# 07_USB_To_UART.net
KiCad netlist of a schematic drawn in Altium Designer
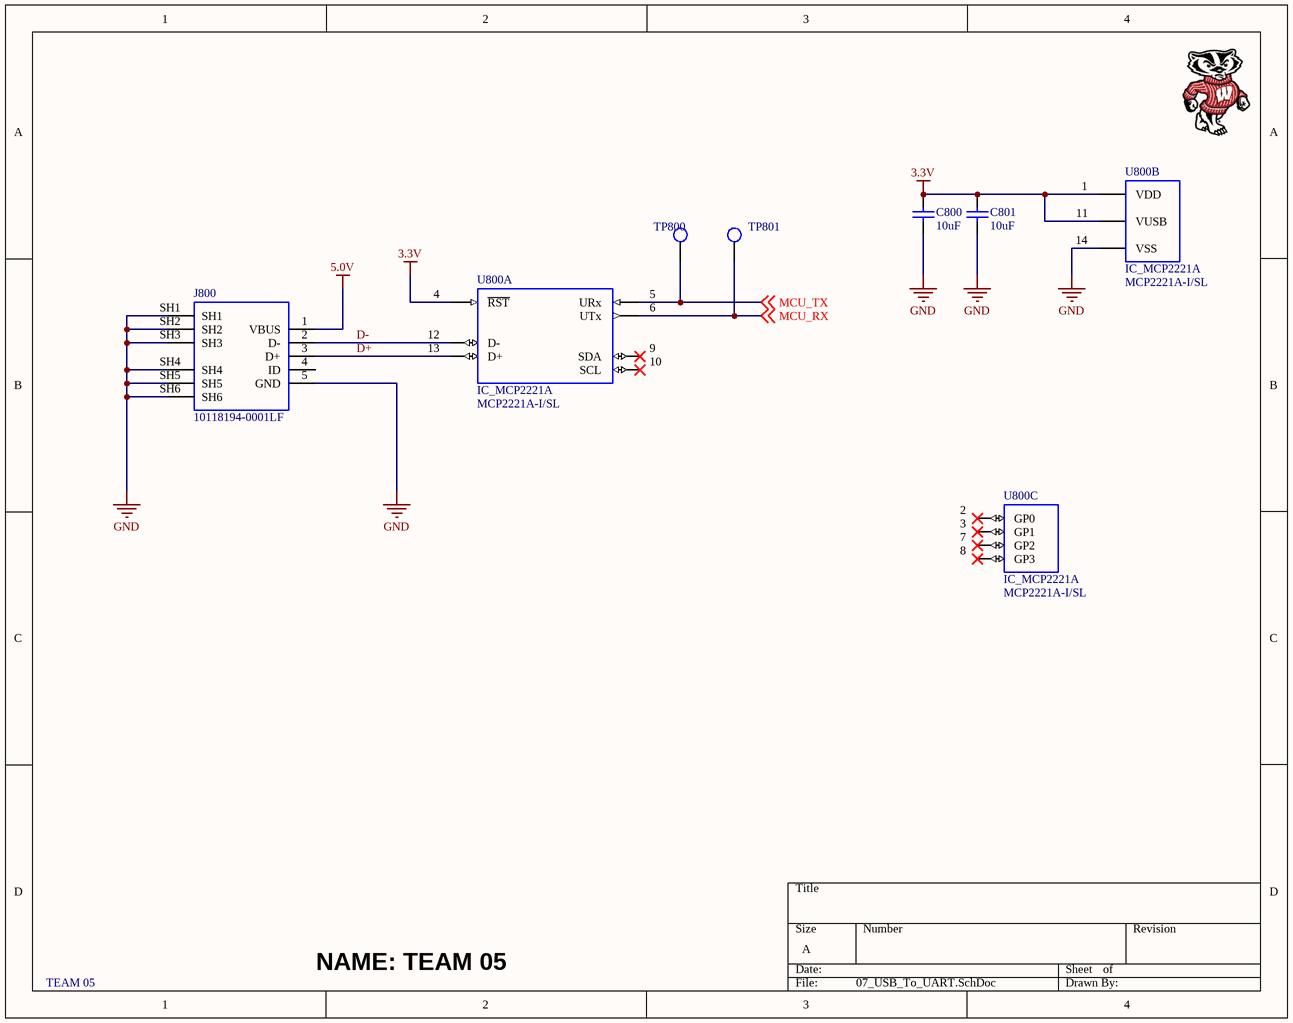
[diagram p0: 07_USB_To_UART.SchDoc]

(export (version "E")
  (design (tool "Eeschema 10.0.6"))
  (components
    (comp (ref "C800")
      (value "10uF")
      (footprint "CAP_0805")
      (description "CAP CER 10UF 16V X7R 0805")
      (fields
        (field (name "MANUFACTURER") "Samsung")
        (field (name "MANUFACTURER PART NUMBER") "CL21A106KPCLQNC")
        (field (name "CAPACITANCE") "10uF")
      )
      (libsource (lib "ece315-S20") (part "CAP_0805_U_010.00"))
    )
    (comp (ref "C801")
      (value "10uF")
      (footprint "CAP_0805")
      (description "CAP CER 10UF 16V X7R 0805")
      (fields
        (field (name "MANUFACTURER") "Samsung")
        (field (name "MANUFACTURER PART NUMBER") "CL21A106KPCLQNC")
        (field (name "CAPACITANCE") "10uF")
      )
      (libsource (lib "ece315-S20") (part "CAP_0805_U_010.00"))
    )
    (comp (ref "J800")
      (value "USB_MICRO_B_10118194-0001LF")
      (footprint "USB_MICRO_B")
      (description "CONN USB MICRO B RECPT SMT R/A")
      (fields
        (field (name "MANUFACTURER") "Amphenol FCI")
        (field (name "MANUFACTURER PART NUMBER") "10118194-0001LF")
      )
      (libsource (lib "ece315-S20") (part "USB_MICRO_B_10118194-0001LF"))
    )
    (comp (ref "TP800")
      (value "TP_1206")
      (footprint "TP-SMC-1206")
      (description "Test Point SMD 1206")
      (fields
        (field (name "MANUFACTURER") "TE Connectivity (Tyco Electronics)")
        (field (name "MANUFACTURER PART NUMBER") "1625854-1")
      )
      (libsource (lib "ece315-S20") (part "TP_1206"))
    )
    (comp (ref "TP801")
      (value "TP_1206")
      (footprint "TP-SMC-1206")
      (description "Test Point SMD 1206")
      (fields
        (field (name "MANUFACTURER") "TE Connectivity (Tyco Electronics)")
        (field (name "MANUFACTURER PART NUMBER") "1625854-1")
      )
      (libsource (lib "ece315-S20") (part "TP_1206"))
    )
    (comp (ref "U800")
      (value "IC_MCP2221A")
      (footprint "SOIC_MCP2221A")
      (description "IC USB TO I2C/UART 14SOIC")
      (fields
        (field (name "MANUFACTURER") "Microchip")
        (field (name "MANUFACTURER PART NUMBER") "MCP2221A-I/SL")
      )
      (libsource (lib "ece315-S20") (part "IC_MCP2221A"))
    )
  )
  (nets
    (net (code "1") (name "/D+") (class "Default")
      (node (ref "J800") (pin "3") (pinfunction "D+_3") (pintype "passive"))
      (node (ref "U800") (pin "13") (pinfunction "D+_13") (pintype "bidirectional"))
    )
    (net (code "2") (name "/D-") (class "Default")
      (node (ref "J800") (pin "2") (pinfunction "D-_2") (pintype "passive"))
      (node (ref "U800") (pin "12") (pinfunction "D-_12") (pintype "bidirectional"))
    )
    (net (code "3") (name "3.3V") (class "Default")
      (node (ref "C800") (pin "1") (pinfunction "1_1") (pintype "passive"))
      (node (ref "C801") (pin "1") (pinfunction "1_1") (pintype "passive"))
      (node (ref "U800") (pin "1") (pinfunction "VDD_1") (pintype "power_in"))
      (node (ref "U800") (pin "11") (pinfunction "VUSB_11") (pintype "power_in"))
      (node (ref "U800") (pin "4") (pinfunction "~{RST}_4") (pintype "input"))
    )
    (net (code "4") (name "5.0V") (class "Default")
      (node (ref "J800") (pin "1") (pinfunction "VBUS_1") (pintype "passive"))
    )
    (net (code "5") (name "GND") (class "Default")
      (node (ref "C800") (pin "2") (pinfunction "2_2") (pintype "passive"))
      (node (ref "C801") (pin "2") (pinfunction "2_2") (pintype "passive"))
      (node (ref "J800") (pin "5") (pinfunction "GND_5") (pintype "passive"))
      (node (ref "J800") (pin "SH1") (pinfunction "SH1_SH1") (pintype "passive"))
      (node (ref "J800") (pin "SH2") (pinfunction "SH2_SH2") (pintype "passive"))
      (node (ref "J800") (pin "SH3") (pinfunction "SH3_SH3") (pintype "passive"))
      (node (ref "J800") (pin "SH4") (pinfunction "SH4_SH4") (pintype "passive"))
      (node (ref "J800") (pin "SH5") (pinfunction "SH5_SH5") (pintype "passive"))
      (node (ref "J800") (pin "SH6") (pinfunction "SH6_SH6") (pintype "passive"))
      (node (ref "U800") (pin "14") (pinfunction "VSS_14") (pintype "power_in"))
    )
    (net (code "6") (name "MCU_RX") (class "Default")
      (node (ref "TP801") (pin "1") (pintype "passive"))
      (node (ref "U800") (pin "6") (pinfunction "UTx_6") (pintype "output"))
    )
    (net (code "7") (name "MCU_TX") (class "Default")
      (node (ref "TP800") (pin "1") (pintype "passive"))
      (node (ref "U800") (pin "5") (pinfunction "URx_5") (pintype "input"))
    )
    (net (code "8") (name "unconnected-(J800-ID-Pad4)") (class "Default")
      (node (ref "J800") (pin "4") (pinfunction "ID_4") (pintype "passive"))
    )
    (net (code "9") (name "unconnected-(U800A-SCL-Pad10)") (class "Default")
      (node (ref "U800") (pin "10") (pinfunction "SCL_10") (pintype "bidirectional+no_connect"))
    )
    (net (code "10") (name "unconnected-(U800A-SDA-Pad9)") (class "Default")
      (node (ref "U800") (pin "9") (pinfunction "SDA_9") (pintype "bidirectional+no_connect"))
    )
    (net (code "11") (name "unconnected-(U800C-GP0-Pad2)") (class "Default")
      (node (ref "U800") (pin "2") (pinfunction "GP0_2") (pintype "bidirectional+no_connect"))
    )
    (net (code "12") (name "unconnected-(U800C-GP1-Pad3)") (class "Default")
      (node (ref "U800") (pin "3") (pinfunction "GP1_3") (pintype "bidirectional+no_connect"))
    )
    (net (code "13") (name "unconnected-(U800C-GP2-Pad7)") (class "Default")
      (node (ref "U800") (pin "7") (pinfunction "GP2_7") (pintype "bidirectional+no_connect"))
    )
    (net (code "14") (name "unconnected-(U800C-GP3-Pad8)") (class "Default")
      (node (ref "U800") (pin "8") (pinfunction "GP3_8") (pintype "bidirectional+no_connect"))
    )
  )
)
